# B171C.net
KiCad netlist of a schematic drawn in EAGLE
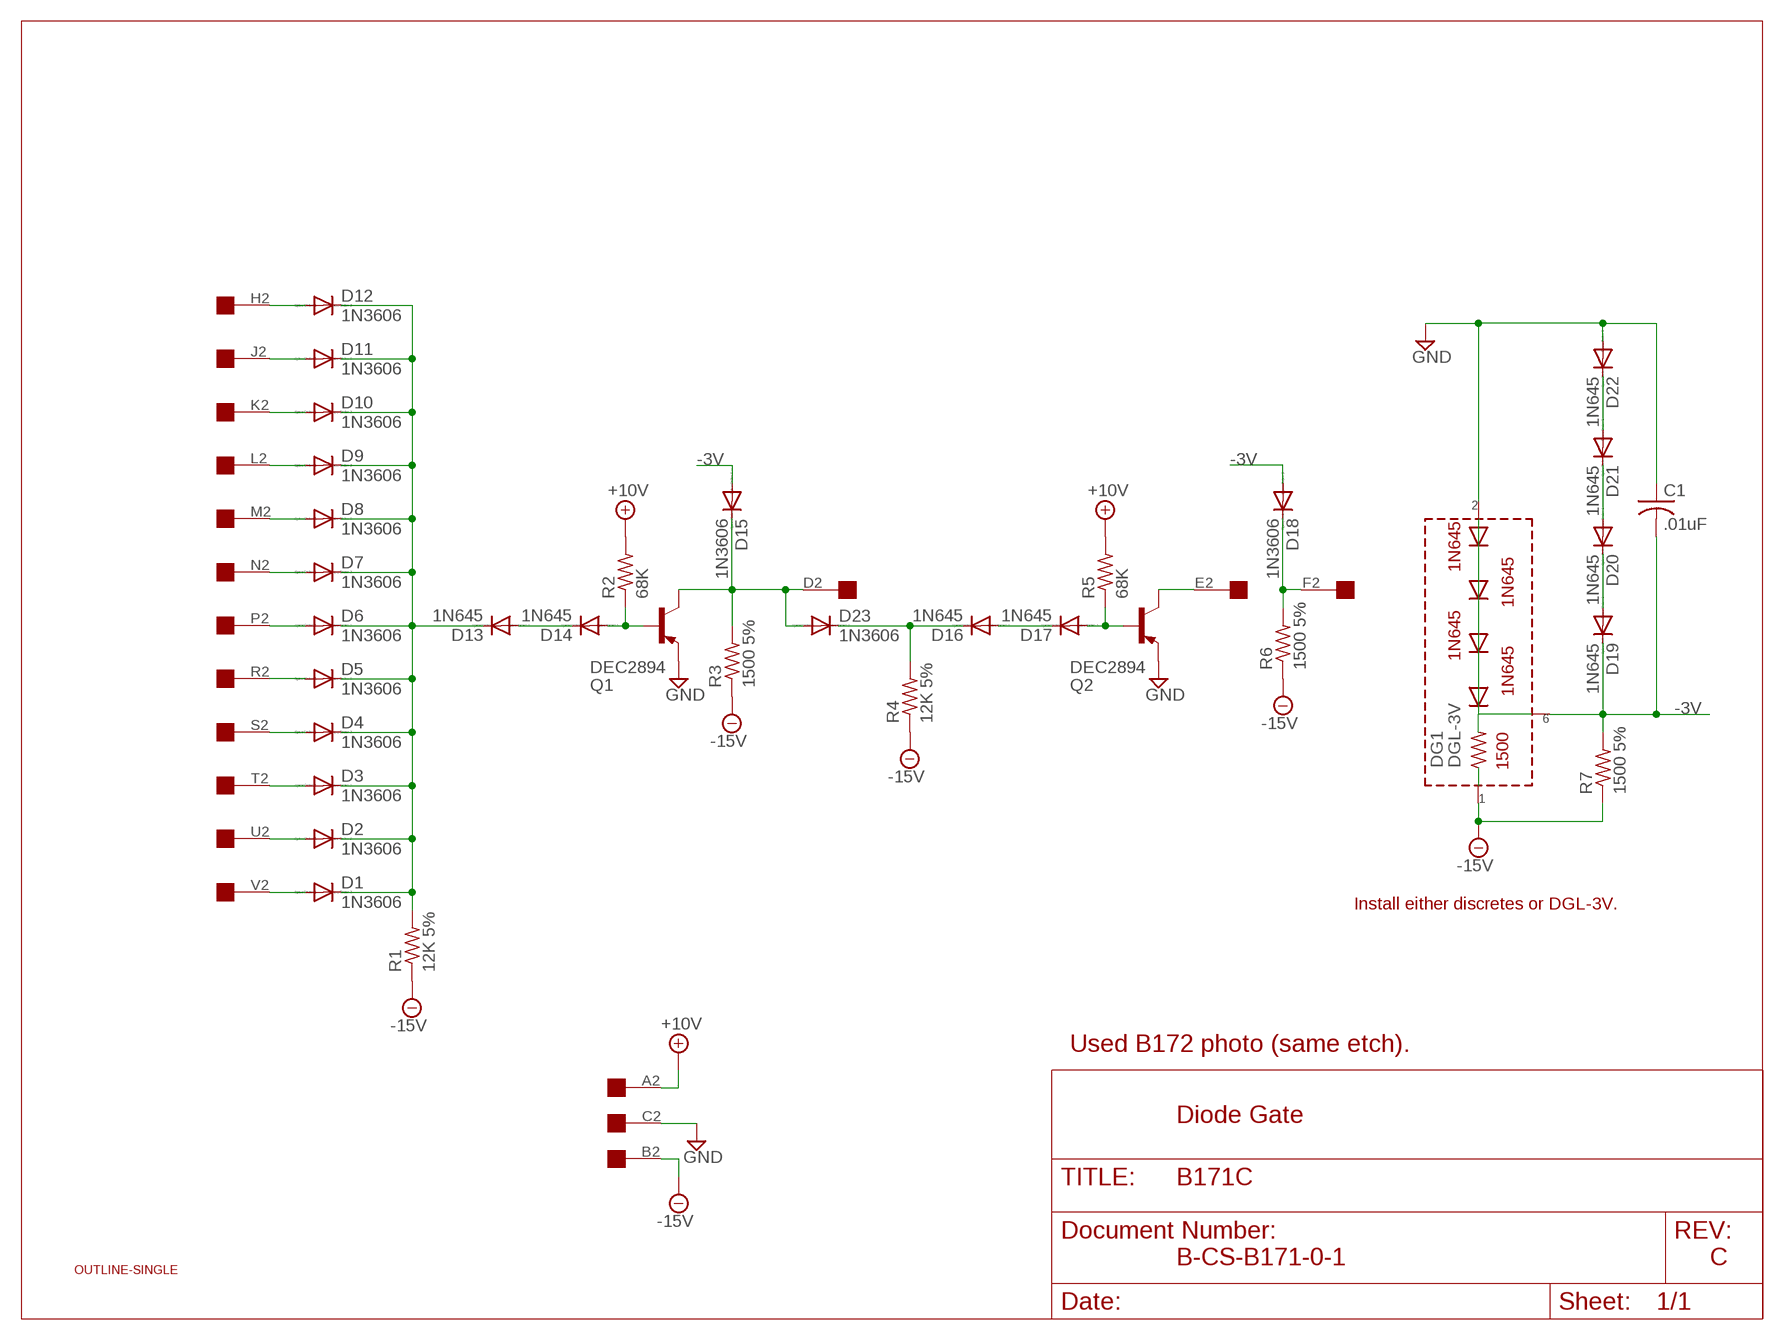
[diagram p0: schematic, sheet 1]

(export (version "E")
  (design (tool "Eeschema 10.0.6"))
  (components
    (comp (ref "C1")
      (value ".01uF")
      (footprint "eagle-import:C050-025X075")
      (libsource (lib "eagle-import") (part "C-US050-025X075"))
    )
    (comp (ref "D1")
      (value "1N3606")
      (footprint "eagle-import:DO35-10")
      (libsource (lib "eagle-import") (part "DIODE-DO35-10"))
    )
    (comp (ref "D2")
      (value "1N3606")
      (footprint "eagle-import:DO35-10")
      (libsource (lib "eagle-import") (part "DIODE-DO35-10"))
    )
    (comp (ref "D3")
      (value "1N3606")
      (footprint "eagle-import:DO35-10")
      (libsource (lib "eagle-import") (part "DIODE-DO35-10"))
    )
    (comp (ref "D4")
      (value "1N3606")
      (footprint "eagle-import:DO35-10")
      (libsource (lib "eagle-import") (part "DIODE-DO35-10"))
    )
    (comp (ref "D5")
      (value "1N3606")
      (footprint "eagle-import:DO35-10")
      (libsource (lib "eagle-import") (part "DIODE-DO35-10"))
    )
    (comp (ref "D6")
      (value "1N3606")
      (footprint "eagle-import:DO35-10")
      (libsource (lib "eagle-import") (part "DIODE-DO35-10"))
    )
    (comp (ref "D7")
      (value "1N3606")
      (footprint "eagle-import:DO35-10")
      (libsource (lib "eagle-import") (part "DIODE-DO35-10"))
    )
    (comp (ref "D8")
      (value "1N3606")
      (footprint "eagle-import:DO35-10")
      (libsource (lib "eagle-import") (part "DIODE-DO35-10"))
    )
    (comp (ref "D9")
      (value "1N3606")
      (footprint "eagle-import:DO35-10")
      (libsource (lib "eagle-import") (part "DIODE-DO35-10"))
    )
    (comp (ref "D10")
      (value "1N3606")
      (footprint "eagle-import:DO35-10")
      (libsource (lib "eagle-import") (part "DIODE-DO35-10"))
    )
    (comp (ref "D11")
      (value "1N3606")
      (footprint "eagle-import:DO35-10")
      (libsource (lib "eagle-import") (part "DIODE-DO35-10"))
    )
    (comp (ref "D12")
      (value "1N3606")
      (footprint "eagle-import:DO35-10")
      (libsource (lib "eagle-import") (part "DIODE-DO35-10"))
    )
    (comp (ref "D13")
      (value "1N645")
      (footprint "eagle-import:DO35-10")
      (libsource (lib "eagle-import") (part "DIODE-DO35-10"))
    )
    (comp (ref "D14")
      (value "1N645")
      (footprint "eagle-import:DO35-10")
      (libsource (lib "eagle-import") (part "DIODE-DO35-10"))
    )
    (comp (ref "D15")
      (value "1N3606")
      (footprint "eagle-import:DO35-10")
      (libsource (lib "eagle-import") (part "DIODE-DO35-10"))
    )
    (comp (ref "D16")
      (value "1N645")
      (footprint "eagle-import:DO35-10")
      (libsource (lib "eagle-import") (part "DIODE-DO35-10"))
    )
    (comp (ref "D17")
      (value "1N645")
      (footprint "eagle-import:DO35-10")
      (libsource (lib "eagle-import") (part "DIODE-DO35-10"))
    )
    (comp (ref "D18")
      (value "1N3606")
      (footprint "eagle-import:DO35-10")
      (libsource (lib "eagle-import") (part "DIODE-DO35-10"))
    )
    (comp (ref "D19")
      (value "1N645")
      (footprint "eagle-import:DO35-10")
      (libsource (lib "eagle-import") (part "DIODE-DO35-10"))
    )
    (comp (ref "D20")
      (value "1N645")
      (footprint "eagle-import:DO35-10")
      (libsource (lib "eagle-import") (part "DIODE-DO35-10"))
    )
    (comp (ref "D21")
      (value "1N645")
      (footprint "eagle-import:DO35-10")
      (libsource (lib "eagle-import") (part "DIODE-DO35-10"))
    )
    (comp (ref "D22")
      (value "1N645")
      (footprint "eagle-import:DO35-10")
      (libsource (lib "eagle-import") (part "DIODE-DO35-10"))
    )
    (comp (ref "D23")
      (value "1N3606")
      (footprint "eagle-import:DO35-10")
      (libsource (lib "eagle-import") (part "DIODE-DO35-10"))
    )
    (comp (ref "DG1")
      (value "DGL-3V")
      (footprint "eagle-import:DGL2")
      (libsource (lib "eagle-import") (part "DGL-3V"))
    )
    (comp (ref "Q1")
      (value "DEC2894")
      (footprint "eagle-import:TO5")
      (libsource (lib "eagle-import") (part "-PNP-TO5"))
    )
    (comp (ref "Q2")
      (value "DEC2894")
      (footprint "eagle-import:TO5")
      (libsource (lib "eagle-import") (part "-PNP-TO5"))
    )
    (comp (ref "R1")
      (value "12K 5%")
      (footprint "eagle-import:0207_10")
      (libsource (lib "eagle-import") (part "R-US_0207/10"))
    )
    (comp (ref "R2")
      (value "68K")
      (footprint "eagle-import:0207_10")
      (libsource (lib "eagle-import") (part "R-US_0207/10"))
    )
    (comp (ref "R3")
      (value "1500 5%")
      (footprint "eagle-import:0207_10")
      (libsource (lib "eagle-import") (part "R-US_0207/10"))
    )
    (comp (ref "R4")
      (value "12K 5%")
      (footprint "eagle-import:0207_10")
      (libsource (lib "eagle-import") (part "R-US_0207/10"))
    )
    (comp (ref "R5")
      (value "68K")
      (footprint "eagle-import:0207_10")
      (libsource (lib "eagle-import") (part "R-US_0207/10"))
    )
    (comp (ref "R6")
      (value "1500 5%")
      (footprint "eagle-import:0207_10")
      (libsource (lib "eagle-import") (part "R-US_0207/10"))
    )
    (comp (ref "R7")
      (value "1500 5%")
      (footprint "eagle-import:0207_10")
      (libsource (lib "eagle-import") (part "R-US_0207/10"))
    )
    (comp (ref "U$1")
      (value "OUTLINE-SINGLE")
      (footprint "eagle-import:SINGLE")
      (libsource (lib "eagle-import") (part "OUTLINE-SINGLE"))
    )
    (comp (ref "U$2")
      (value "EDGE-1")
      (footprint "eagle-import:EDGE-CON1")
      (libsource (lib "eagle-import") (part "EDGE-1"))
    )
  )
  (nets
    (net (code "1") (name "+10V") (class "Default")
      (node (ref "R2") (pin "2") (pinfunction "2_2") (pintype "passive"))
      (node (ref "R5") (pin "2") (pinfunction "2_2") (pintype "passive"))
      (node (ref "U$2") (pin "A2") (pinfunction "1_A2") (pintype "bidirectional"))
    )
    (net (code "2") (name "-15V") (class "Default")
      (node (ref "DG1") (pin "P$1") (pinfunction "1_P$1") (pintype "passive"))
      (node (ref "R1") (pin "1") (pinfunction "1_1") (pintype "passive"))
      (node (ref "R3") (pin "1") (pinfunction "1_1") (pintype "passive"))
      (node (ref "R4") (pin "1") (pinfunction "1_1") (pintype "passive"))
      (node (ref "R6") (pin "1") (pinfunction "1_1") (pintype "passive"))
      (node (ref "R7") (pin "1") (pinfunction "1_1") (pintype "passive"))
      (node (ref "U$2") (pin "B2") (pinfunction "1_B2") (pintype "bidirectional"))
    )
    (net (code "3") (name "/-3V") (class "Default")
      (node (ref "C1") (pin "2") (pinfunction "2_2") (pintype "passive"))
      (node (ref "D15") (pin "A") (pinfunction "A_A") (pintype "passive"))
      (node (ref "D18") (pin "A") (pinfunction "A_A") (pintype "passive"))
      (node (ref "D19") (pin "C") (pinfunction "C_C") (pintype "passive"))
      (node (ref "DG1") (pin "P$6") (pinfunction "6_P$6") (pintype "passive"))
      (node (ref "R7") (pin "2") (pinfunction "2_2") (pintype "passive"))
    )
    (net (code "4") (name "GND") (class "Default")
      (node (ref "C1") (pin "1") (pinfunction "1_1") (pintype "passive"))
      (node (ref "D22") (pin "A") (pinfunction "A_A") (pintype "passive"))
      (node (ref "DG1") (pin "P$2") (pinfunction "2_P$2") (pintype "passive"))
      (node (ref "Q1") (pin "1") (pinfunction "E_1") (pintype "passive"))
      (node (ref "Q2") (pin "1") (pinfunction "E_1") (pintype "passive"))
      (node (ref "U$2") (pin "C2") (pinfunction "1_C2") (pintype "bidirectional"))
    )
    (net (code "5") (name "Net-(D1-PadC)") (class "Default")
      (node (ref "D1") (pin "C") (pinfunction "C_C") (pintype "passive"))
      (node (ref "D10") (pin "C") (pinfunction "C_C") (pintype "passive"))
      (node (ref "D11") (pin "C") (pinfunction "C_C") (pintype "passive"))
      (node (ref "D12") (pin "C") (pinfunction "C_C") (pintype "passive"))
      (node (ref "D13") (pin "C") (pinfunction "C_C") (pintype "passive"))
      (node (ref "D2") (pin "C") (pinfunction "C_C") (pintype "passive"))
      (node (ref "D3") (pin "C") (pinfunction "C_C") (pintype "passive"))
      (node (ref "D4") (pin "C") (pinfunction "C_C") (pintype "passive"))
      (node (ref "D5") (pin "C") (pinfunction "C_C") (pintype "passive"))
      (node (ref "D6") (pin "C") (pinfunction "C_C") (pintype "passive"))
      (node (ref "D7") (pin "C") (pinfunction "C_C") (pintype "passive"))
      (node (ref "D8") (pin "C") (pinfunction "C_C") (pintype "passive"))
      (node (ref "D9") (pin "C") (pinfunction "C_C") (pintype "passive"))
      (node (ref "R1") (pin "2") (pinfunction "2_2") (pintype "passive"))
    )
    (net (code "6") (name "Net-(D13-PadA)") (class "Default")
      (node (ref "D13") (pin "A") (pinfunction "A_A") (pintype "passive"))
      (node (ref "D14") (pin "C") (pinfunction "C_C") (pintype "passive"))
    )
    (net (code "7") (name "Net-(D16-PadA)") (class "Default")
      (node (ref "D16") (pin "A") (pinfunction "A_A") (pintype "passive"))
      (node (ref "D17") (pin "C") (pinfunction "C_C") (pintype "passive"))
    )
    (net (code "8") (name "Net-(D16-PadC)") (class "Default")
      (node (ref "D16") (pin "C") (pinfunction "C_C") (pintype "passive"))
      (node (ref "D23") (pin "C") (pinfunction "C_C") (pintype "passive"))
      (node (ref "R4") (pin "2") (pinfunction "2_2") (pintype "passive"))
    )
    (net (code "9") (name "Net-(D19-PadA)") (class "Default")
      (node (ref "D19") (pin "A") (pinfunction "A_A") (pintype "passive"))
      (node (ref "D20") (pin "C") (pinfunction "C_C") (pintype "passive"))
    )
    (net (code "10") (name "Net-(D20-PadA)") (class "Default")
      (node (ref "D20") (pin "A") (pinfunction "A_A") (pintype "passive"))
      (node (ref "D21") (pin "C") (pinfunction "C_C") (pintype "passive"))
    )
    (net (code "11") (name "Net-(D21-PadA)") (class "Default")
      (node (ref "D21") (pin "A") (pinfunction "A_A") (pintype "passive"))
      (node (ref "D22") (pin "C") (pinfunction "C_C") (pintype "passive"))
    )
    (net (code "12") (name "Net-(Q1-B)") (class "Default")
      (node (ref "D14") (pin "A") (pinfunction "A_A") (pintype "passive"))
      (node (ref "Q1") (pin "2") (pinfunction "B_2") (pintype "passive"))
      (node (ref "R2") (pin "1") (pinfunction "1_1") (pintype "passive"))
    )
    (net (code "13") (name "Net-(Q1-C)") (class "Default")
      (node (ref "D15") (pin "C") (pinfunction "C_C") (pintype "passive"))
      (node (ref "D23") (pin "A") (pinfunction "A_A") (pintype "passive"))
      (node (ref "Q1") (pin "3") (pinfunction "C_3") (pintype "passive"))
      (node (ref "R3") (pin "2") (pinfunction "2_2") (pintype "passive"))
      (node (ref "U$2") (pin "D2") (pinfunction "1_D2") (pintype "bidirectional"))
    )
    (net (code "14") (name "Net-(Q2-B)") (class "Default")
      (node (ref "D17") (pin "A") (pinfunction "A_A") (pintype "passive"))
      (node (ref "Q2") (pin "2") (pinfunction "B_2") (pintype "passive"))
      (node (ref "R5") (pin "1") (pinfunction "1_1") (pintype "passive"))
    )
    (net (code "15") (name "Net-(Q2-C)") (class "Default")
      (node (ref "Q2") (pin "3") (pinfunction "C_3") (pintype "passive"))
      (node (ref "U$2") (pin "E2") (pinfunction "1_E2") (pintype "bidirectional"))
    )
    (net (code "16") (name "Net-(U$2F-1)") (class "Default")
      (node (ref "D18") (pin "C") (pinfunction "C_C") (pintype "passive"))
      (node (ref "R6") (pin "2") (pinfunction "2_2") (pintype "passive"))
      (node (ref "U$2") (pin "F2") (pinfunction "1_F2") (pintype "bidirectional"))
    )
    (net (code "17") (name "Net-(U$2G-1)") (class "Default")
      (node (ref "D12") (pin "A") (pinfunction "A_A") (pintype "passive"))
      (node (ref "U$2") (pin "H2") (pinfunction "1_H2") (pintype "bidirectional"))
    )
    (net (code "18") (name "Net-(U$2H-1)") (class "Default")
      (node (ref "D11") (pin "A") (pinfunction "A_A") (pintype "passive"))
      (node (ref "U$2") (pin "J2") (pinfunction "1_J2") (pintype "bidirectional"))
    )
    (net (code "19") (name "Net-(U$2I-1)") (class "Default")
      (node (ref "D10") (pin "A") (pinfunction "A_A") (pintype "passive"))
      (node (ref "U$2") (pin "K2") (pinfunction "1_K2") (pintype "bidirectional"))
    )
    (net (code "20") (name "Net-(U$2J-1)") (class "Default")
      (node (ref "D9") (pin "A") (pinfunction "A_A") (pintype "passive"))
      (node (ref "U$2") (pin "L2") (pinfunction "1_L2") (pintype "bidirectional"))
    )
    (net (code "21") (name "Net-(U$2K-1)") (class "Default")
      (node (ref "D8") (pin "A") (pinfunction "A_A") (pintype "passive"))
      (node (ref "U$2") (pin "M2") (pinfunction "1_M2") (pintype "bidirectional"))
    )
    (net (code "22") (name "Net-(U$2L-1)") (class "Default")
      (node (ref "D7") (pin "A") (pinfunction "A_A") (pintype "passive"))
      (node (ref "U$2") (pin "N2") (pinfunction "1_N2") (pintype "bidirectional"))
    )
    (net (code "23") (name "Net-(U$2M-1)") (class "Default")
      (node (ref "D6") (pin "A") (pinfunction "A_A") (pintype "passive"))
      (node (ref "U$2") (pin "P2") (pinfunction "1_P2") (pintype "bidirectional"))
    )
    (net (code "24") (name "Net-(U$2N-1)") (class "Default")
      (node (ref "D5") (pin "A") (pinfunction "A_A") (pintype "passive"))
      (node (ref "U$2") (pin "R2") (pinfunction "1_R2") (pintype "bidirectional"))
    )
    (net (code "25") (name "Net-(U$2O-1)") (class "Default")
      (node (ref "D4") (pin "A") (pinfunction "A_A") (pintype "passive"))
      (node (ref "U$2") (pin "S2") (pinfunction "1_S2") (pintype "bidirectional"))
    )
    (net (code "26") (name "Net-(U$2P-1)") (class "Default")
      (node (ref "D3") (pin "A") (pinfunction "A_A") (pintype "passive"))
      (node (ref "U$2") (pin "T2") (pinfunction "1_T2") (pintype "bidirectional"))
    )
    (net (code "27") (name "Net-(U$2Q-1)") (class "Default")
      (node (ref "D2") (pin "A") (pinfunction "A_A") (pintype "passive"))
      (node (ref "U$2") (pin "U2") (pinfunction "1_U2") (pintype "bidirectional"))
    )
    (net (code "28") (name "Net-(U$2R-1)") (class "Default")
      (node (ref "D1") (pin "A") (pinfunction "A_A") (pintype "passive"))
      (node (ref "U$2") (pin "V2") (pinfunction "1_V2") (pintype "bidirectional"))
    )
  )
)
